# CheerLights1Channel.net
KiCad netlist of a schematic drawn in EAGLE
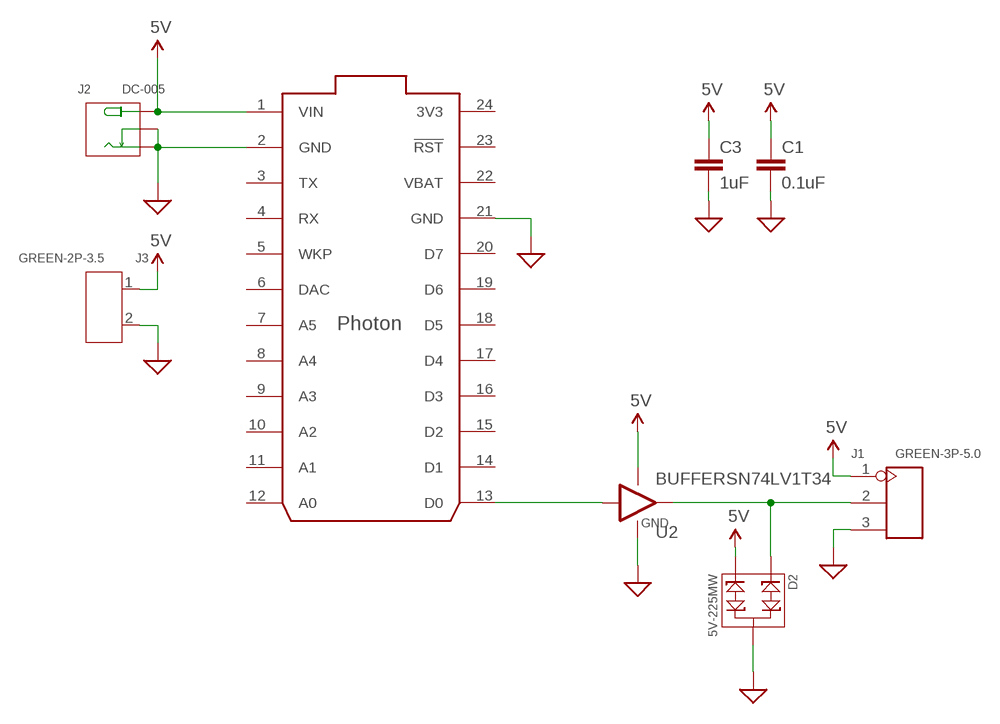
[diagram p0: schematic, sheet 1]

(export (version "E")
  (design (tool "Eeschema 10.0.6"))
  (components
    (comp (ref "C1")
      (value "0.1uF")
      (footprint "eagle-import:0805")
      (libsource (lib "eagle-import") (part "CAP0805"))
    )
    (comp (ref "C3")
      (value "1uF")
      (footprint "eagle-import:0805")
      (libsource (lib "eagle-import") (part "CAP0805"))
    )
    (comp (ref "D2")
      (value "5V-225MW")
      (footprint "eagle-import:SOT-23")
      (fields (field (name "MPN") "CESD5V0AP") (field (name "PARTNO") "TPD2E009DBZR"))
      (libsource (lib "eagle-import") (part "SMD-DIODE-TVS-5V-225MW(SOT-23)"))
    )
    (comp (ref "J1")
      (value "GREEN-3P-5.0")
      (footprint "eagle-import:H3-5.0-15.5X8.0MM")
      (fields (field (name "PARTNO") "1935174"))
      (libsource (lib "eagle-import") (part "SCREW-TERMINAL-GREEN(3P-5.0)"))
    )
    (comp (ref "J2")
      (value "DC-005")
      (footprint "eagle-import:DCJ3P-14.2X11.0X9.0MM")
      (fields (field (name "PARTNO") "EJ508A"))
      (libsource (lib "eagle-import") (part "CONN-POWER-JACK-2.1MM(DC-005)"))
    )
    (comp (ref "J3")
      (value "GREEN-2P-3.5")
      (footprint "eagle-import:H2-3.5-7.0X7.0MM")
      (libsource (lib "eagle-import") (part "SCREW-TERMINAL-GREEN(2P-3.5)"))
    )
    (comp (ref "U1")
      (value "PHOTON_WITH_HEADERS")
      (footprint "eagle-import:PHOTON")
      (libsource (lib "eagle-import") (part "PHOTON_WITH_HEADERS"))
    )
    (comp (ref "U2")
      (value "BUFFERSN74LV1T34")
      (footprint "eagle-import:SOT23-5")
      (libsource (lib "eagle-import") (part "BUFFERSN74LV1T34"))
    )
  )
  (nets
    (net (code "1") (name "/3V3") (class "Default")
      (node (ref "U1") (pin "24") (pinfunction "3V3_24") (pintype "power_in"))
    )
    (net (code "2") (name "/VBAT") (class "Default")
      (node (ref "U1") (pin "22") (pinfunction "VBAT_22") (pintype "power_in"))
    )
    (net (code "3") (name "5V") (class "Default")
      (node (ref "C1") (pin "1") (pinfunction "1_1") (pintype "passive"))
      (node (ref "C3") (pin "1") (pinfunction "1_1") (pintype "passive"))
      (node (ref "D2") (pin "2") (pinfunction "2_2") (pintype "power_in"))
      (node (ref "J1") (pin "1") (pinfunction "P$1_1") (pintype "bidirectional"))
      (node (ref "J2") (pin "+") (pinfunction "+_+") (pintype "bidirectional"))
      (node (ref "J3") (pin "1") (pinfunction "1_1") (pintype "bidirectional"))
      (node (ref "U1") (pin "1") (pinfunction "VIN_1") (pintype "power_in"))
      (node (ref "U2") (pin "5") (pinfunction "PWR_5") (pintype "power_in"))
    )
    (net (code "4") (name "GND") (class "Default")
      (node (ref "C1") (pin "2") (pinfunction "2_2") (pintype "passive"))
      (node (ref "C3") (pin "2") (pinfunction "2_2") (pintype "passive"))
      (node (ref "D2") (pin "3") (pinfunction "3_3") (pintype "bidirectional"))
      (node (ref "J1") (pin "3") (pinfunction "P$3_3") (pintype "bidirectional"))
      (node (ref "J2") (pin "-1") (pinfunction "-_-1") (pintype "bidirectional"))
      (node (ref "J2") (pin "-2") (pinfunction "CDN_-2") (pintype "bidirectional"))
      (node (ref "J3") (pin "2") (pinfunction "2_2") (pintype "bidirectional"))
      (node (ref "U1") (pin "2") (pinfunction "GND_2") (pintype "power_in"))
      (node (ref "U1") (pin "21") (pinfunction "GND_21") (pintype "power_in"))
      (node (ref "U2") (pin "3") (pinfunction "GND_3") (pintype "power_in"))
    )
    (net (code "5") (name "Net-(J1-P$2)") (class "Default")
      (node (ref "D2") (pin "1") (pinfunction "1_1") (pintype "power_in"))
      (node (ref "J1") (pin "2") (pinfunction "P$2_2") (pintype "bidirectional"))
      (node (ref "U2") (pin "4") (pinfunction "OUT_4") (pintype "output"))
    )
    (net (code "6") (name "Net-(U1-D0)") (class "Default")
      (node (ref "U1") (pin "13") (pinfunction "D0_13") (pintype "bidirectional"))
      (node (ref "U2") (pin "2") (pinfunction "IN_2") (pintype "input"))
    )
    (net (code "7") (name "unconnected-(U1-A0-Pad12)") (class "Default")
      (node (ref "U1") (pin "12") (pinfunction "A0_12") (pintype "bidirectional"))
    )
    (net (code "8") (name "unconnected-(U1-A1-Pad11)") (class "Default")
      (node (ref "U1") (pin "11") (pinfunction "A1_11") (pintype "bidirectional"))
    )
    (net (code "9") (name "unconnected-(U1-A2-Pad10)") (class "Default")
      (node (ref "U1") (pin "10") (pinfunction "A2_10") (pintype "bidirectional"))
    )
    (net (code "10") (name "unconnected-(U1-A3-Pad9)") (class "Default")
      (node (ref "U1") (pin "9") (pinfunction "A3_9") (pintype "bidirectional"))
    )
    (net (code "11") (name "unconnected-(U1-A4-Pad8)") (class "Default")
      (node (ref "U1") (pin "8") (pinfunction "A4_8") (pintype "bidirectional"))
    )
    (net (code "12") (name "unconnected-(U1-A5-Pad7)") (class "Default")
      (node (ref "U1") (pin "7") (pinfunction "A5_7") (pintype "bidirectional"))
    )
    (net (code "13") (name "unconnected-(U1-D1-Pad14)") (class "Default")
      (node (ref "U1") (pin "14") (pinfunction "D1_14") (pintype "bidirectional"))
    )
    (net (code "14") (name "unconnected-(U1-D2-Pad15)") (class "Default")
      (node (ref "U1") (pin "15") (pinfunction "D2_15") (pintype "bidirectional"))
    )
    (net (code "15") (name "unconnected-(U1-D3-Pad16)") (class "Default")
      (node (ref "U1") (pin "16") (pinfunction "D3_16") (pintype "bidirectional"))
    )
    (net (code "16") (name "unconnected-(U1-D4-Pad17)") (class "Default")
      (node (ref "U1") (pin "17") (pinfunction "D4_17") (pintype "bidirectional"))
    )
    (net (code "17") (name "unconnected-(U1-D5-Pad18)") (class "Default")
      (node (ref "U1") (pin "18") (pinfunction "D5_18") (pintype "bidirectional"))
    )
    (net (code "18") (name "unconnected-(U1-D6-Pad19)") (class "Default")
      (node (ref "U1") (pin "19") (pinfunction "D6_19") (pintype "bidirectional"))
    )
    (net (code "19") (name "unconnected-(U1-D7-Pad20)") (class "Default")
      (node (ref "U1") (pin "20") (pinfunction "D7_20") (pintype "bidirectional"))
    )
    (net (code "20") (name "unconnected-(U1-DAC-Pad6)") (class "Default")
      (node (ref "U1") (pin "6") (pinfunction "DAC_6") (pintype "bidirectional"))
    )
    (net (code "21") (name "unconnected-(U1-RX-Pad4)") (class "Default")
      (node (ref "U1") (pin "4") (pinfunction "RX_4") (pintype "bidirectional"))
    )
    (net (code "22") (name "unconnected-(U1-TX-Pad3)") (class "Default")
      (node (ref "U1") (pin "3") (pinfunction "TX_3") (pintype "bidirectional"))
    )
    (net (code "23") (name "unconnected-(U1-WKP-Pad5)") (class "Default")
      (node (ref "U1") (pin "5") (pinfunction "WKP_5") (pintype "bidirectional"))
    )
    (net (code "24") (name "unconnected-(U1-~{RST}-Pad23)") (class "Default")
      (node (ref "U1") (pin "23") (pinfunction "~{RST}_23") (pintype "bidirectional"))
    )
  )
)
